# I2C_Isolator.net
KiCad netlist of a schematic drawn in Altium Designer
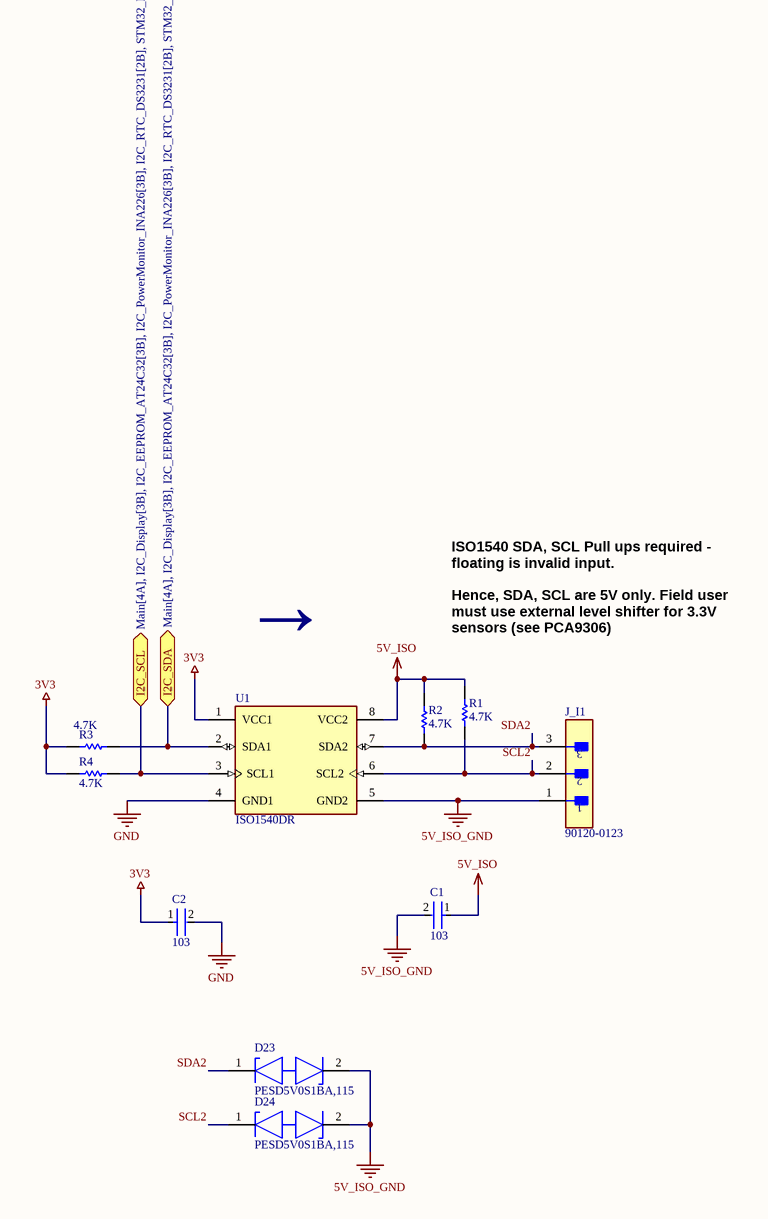
[diagram p0: I2C_Isolator.SchDoc]

(export (version "E")
  (design (tool "Eeschema 10.0.6"))
  (components
    (comp (ref "C1")
      (value "103")
      (footprint "FP-CC0603-DA-MFG")
      (description "CAP CER 0.1UF 16V X7R 0603")
      (fields
        (field (name "OCTOPART") "https://octopart.com/cc0603krx7r7bb104-yageo-192941")
        (field (name "TOLERANCE") "0.1")
      )
      (libsource (lib "Altium Content Vault") (part "11868f565c42a9108669ba33697ecf6"))
    )
    (comp (ref "C2")
      (value "103")
      (footprint "FP-CC0603-DA-MFG")
      (description "CAP CER 0.1UF 16V X7R 0603")
      (fields
        (field (name "OCTOPART") "https://octopart.com/cc0603krx7r7bb104-yageo-192941")
        (field (name "TOLERANCE") "0.1")
      )
      (libsource (lib "Altium Content Vault") (part "11868f565c42a9108669ba33697ecf6"))
    )
    (comp (ref "D23")
      (value "PESD5V0S1BA,115")
      (footprint "FP-SOD323-CA-MFG")
      (description "TVS DIODE 5V 14V SOD323")
      (libsource (lib "Altium Content Vault") (part "f6dbb2535d6b2d347ec798cb4d032a4"))
    )
    (comp (ref "D24")
      (value "PESD5V0S1BA,115")
      (footprint "FP-SOD323-CA-MFG")
      (description "TVS DIODE 5V 14V SOD323")
      (libsource (lib "Altium Content Vault") (part "f6dbb2535d6b2d347ec798cb4d032a4"))
    )
    (comp (ref "J_I1")
      (value "90120-0123")
      (footprint "FP-90120-0123-MFG")
      (description "CONN HEADER VERT 3POS 2.54MM")
      (libsource (lib "Altium Content Vault") (part "0d3f023dd272f625e17a2be33dea85f"))
    )
    (comp (ref "R1")
      (value "4.7K")
      (footprint "RESC1608X55X25ML10T15")
      (description "Chip Resistor, 4.7 KOhm, +/- 5%, 100 mW, -55 to 155 degC, 0603 (1608 Metric), RoHS, Tape and Reel")
      (fields (field (name "TOLERANCE") "5%") (field (name "MANUFACTURER") "Yageo"))
      (libsource (lib "Altium Content Vault") (part "RES-2"))
    )
    (comp (ref "R2")
      (value "4.7K")
      (footprint "RESC1608X55X25ML10T15")
      (description "Chip Resistor, 4.7 KOhm, +/- 5%, 100 mW, -55 to 155 degC, 0603 (1608 Metric), RoHS, Tape and Reel")
      (fields (field (name "TOLERANCE") "5%") (field (name "MANUFACTURER") "Yageo"))
      (libsource (lib "Altium Content Vault") (part "RES-2"))
    )
    (comp (ref "R3")
      (value "4.7K")
      (footprint "RESC1608X55X25ML10T15")
      (description "Chip Resistor, 4.7 KOhm, +/- 5%, 100 mW, -55 to 155 degC, 0603 (1608 Metric), RoHS, Tape and Reel")
      (fields (field (name "TOLERANCE") "5%") (field (name "MANUFACTURER") "Yageo"))
      (libsource (lib "Altium Content Vault") (part "RES-2"))
    )
    (comp (ref "R4")
      (value "4.7K")
      (footprint "RESC1608X55X25ML10T15")
      (description "Chip Resistor, 4.7 KOhm, +/- 5%, 100 mW, -55 to 155 degC, 0603 (1608 Metric), RoHS, Tape and Reel")
      (fields (field (name "TOLERANCE") "5%") (field (name "MANUFACTURER") "Yageo"))
      (libsource (lib "Altium Content Vault") (part "RES-2"))
    )
    (comp (ref "U1")
      (value "ISO1540DR")
      (footprint "FP-D0008A-MFG")
      (description "DGTL ISO 2.5KV 2CH I2C 8SOIC")
      (fields
        (field (name "OCTOPART") "https://octopart.com/iso1540dr-texas+instruments-24334113")
        (field (name "MANUFACTURER") "Texas Instruments")
      )
      (libsource (lib "Altium Content Vault") (part "d824faccee5d143ad01692c0ddd1d85"))
    )
  )
  (nets
    (net (code "1") (name "/I2C_SCL") (class "Default")
      (node (ref "R4") (pin "1") (pinfunction "1_1") (pintype "passive"))
      (node (ref "U1") (pin "3") (pinfunction "SCL1_3") (pintype "input"))
    )
    (net (code "2") (name "/I2C_SDA") (class "Default")
      (node (ref "R3") (pin "1") (pinfunction "1_1") (pintype "passive"))
      (node (ref "U1") (pin "2") (pinfunction "SDA1_2") (pintype "bidirectional"))
    )
    (net (code "3") (name "/SCL2") (class "Default")
      (node (ref "D24") (pin "1") (pinfunction "K1_1") (pintype "passive"))
      (node (ref "J_I1") (pin "2") (pinfunction "2_2") (pintype "passive"))
      (node (ref "R1") (pin "1") (pinfunction "1_1") (pintype "passive"))
      (node (ref "U1") (pin "6") (pinfunction "SCL2_6") (pintype "input"))
    )
    (net (code "4") (name "/SDA2") (class "Default")
      (node (ref "D23") (pin "1") (pinfunction "K1_1") (pintype "passive"))
      (node (ref "J_I1") (pin "3") (pinfunction "3_3") (pintype "passive"))
      (node (ref "R2") (pin "1") (pinfunction "1_1") (pintype "passive"))
      (node (ref "U1") (pin "7") (pinfunction "SDA2_7") (pintype "bidirectional"))
    )
    (net (code "5") (name "3V3") (class "Default")
      (node (ref "C2") (pin "1") (pinfunction "1_1") (pintype "passive"))
      (node (ref "R3") (pin "2") (pinfunction "2_2") (pintype "passive"))
      (node (ref "R4") (pin "2") (pinfunction "2_2") (pintype "passive"))
      (node (ref "U1") (pin "1") (pinfunction "VCC1_1") (pintype "power_in"))
    )
    (net (code "6") (name "5V_ISO") (class "Default")
      (node (ref "C1") (pin "1") (pinfunction "1_1") (pintype "passive"))
      (node (ref "R1") (pin "2") (pinfunction "2_2") (pintype "passive"))
      (node (ref "R2") (pin "2") (pinfunction "2_2") (pintype "passive"))
      (node (ref "U1") (pin "8") (pinfunction "VCC2_8") (pintype "power_in"))
    )
    (net (code "7") (name "5V_ISO_GND") (class "Default")
      (node (ref "C1") (pin "2") (pinfunction "2_2") (pintype "passive"))
      (node (ref "D23") (pin "2") (pinfunction "K2_2") (pintype "passive"))
      (node (ref "D24") (pin "2") (pinfunction "K2_2") (pintype "passive"))
      (node (ref "J_I1") (pin "1") (pinfunction "1_1") (pintype "passive"))
      (node (ref "U1") (pin "5") (pinfunction "GND2_5") (pintype "power_in"))
    )
    (net (code "8") (name "GND") (class "Default")
      (node (ref "C2") (pin "2") (pinfunction "2_2") (pintype "passive"))
      (node (ref "U1") (pin "4") (pinfunction "GND1_4") (pintype "power_in"))
    )
  )
)
